# WIFI_Module_Page.net
KiCad netlist of a schematic drawn in Altium Designer
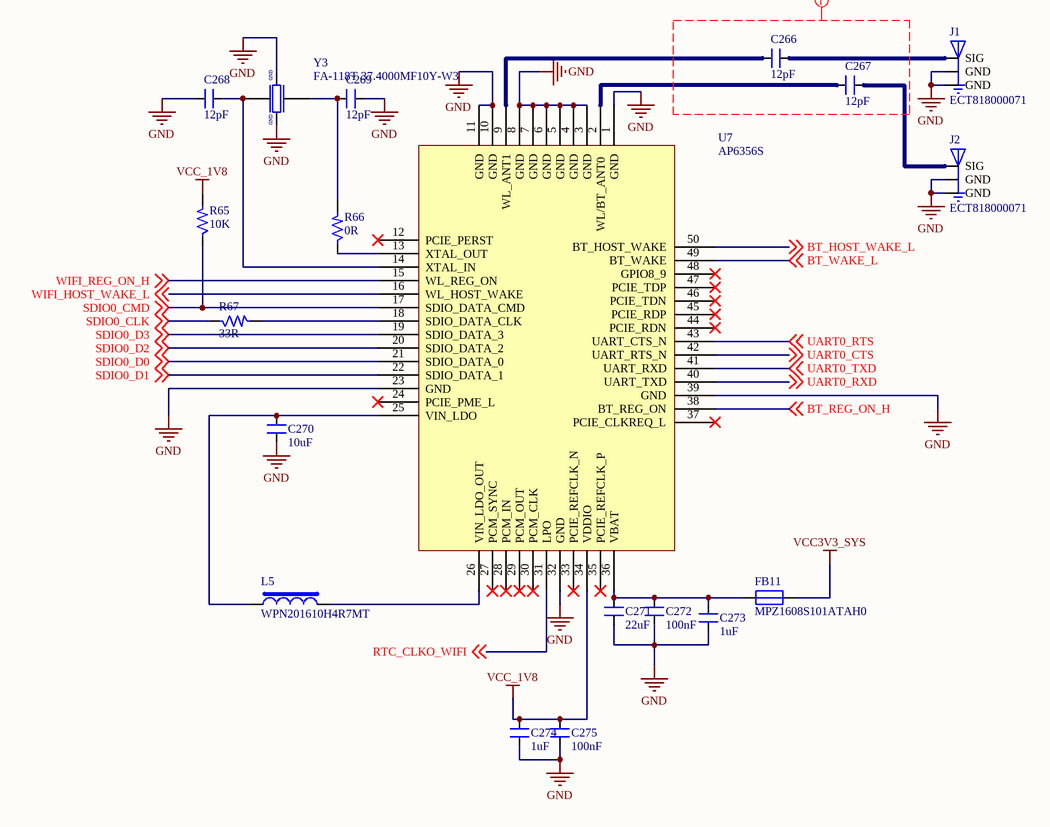
[diagram p0: WIFI Module Page.SchDoc]

(export (version "E")
  (design (tool "Eeschema 10.0.6"))
  (components
    (comp (ref "C266")
      (value "12pF")
      (footprint "CAP_0603")
      (description "12pF ±10% 10V Ceramic Capacitor X8R 0603 (1608 Metric)")
      (fields
        (field (name "MANUFACTURER") "KEMET")
        (field (name "MANUFACTURER PART NUMBER") "C0603X120K8HAC7867")
      )
      (libsource (lib "RK3399 _Module_Schlib") (part "CAP_12pF-10V-10%-0603"))
    )
    (comp (ref "C267")
      (value "12pF")
      (footprint "CAP_0603")
      (description "12pF ±10% 10V Ceramic Capacitor X8R 0603 (1608 Metric)")
      (fields
        (field (name "MANUFACTURER") "KEMET")
        (field (name "MANUFACTURER PART NUMBER") "C0603X120K8HAC7867")
      )
      (libsource (lib "RK3399 _Module_Schlib") (part "CAP_12pF-10V-10%-0603"))
    )
    (comp (ref "C268")
      (value "12pF")
      (footprint "CAP_0603")
      (description "12pF ±10% 10V Ceramic Capacitor X8R 0603 (1608 Metric)")
      (fields
        (field (name "MANUFACTURER") "KEMET")
        (field (name "MANUFACTURER PART NUMBER") "C0603X120K8HAC7867")
      )
      (libsource (lib "RK3399 _Module_Schlib") (part "CAP_12pF-10V-10%-0603"))
    )
    (comp (ref "C269")
      (value "12pF")
      (footprint "CAP_0603")
      (description "12pF ±10% 10V Ceramic Capacitor X8R 0603 (1608 Metric)")
      (fields
        (field (name "MANUFACTURER") "KEMET")
        (field (name "MANUFACTURER PART NUMBER") "C0603X120K8HAC7867")
      )
      (libsource (lib "RK3399 _Module_Schlib") (part "CAP_12pF-10V-10%-0603"))
    )
    (comp (ref "C270")
      (value "10uF")
      (footprint "CAP_0603")
      (description "10µF ±10% 10V Ceramic Capacitor X5R 0603 (1608 Metric)")
      (fields
        (field (name "MANUFACTURER PART NUMBER") "GRM188R61A106KE69J")
        (field (name "MANUFACTURER") "Murata Electronics")
      )
      (libsource (lib "RK3399 _Module_Schlib") (part "CAP_10uF-10V-10%-0603"))
    )
    (comp (ref "C271")
      (value "22uF")
      (footprint "CAP_0603")
      (description "22µF ±20% 10V Ceramic Capacitor X5R 0603 (1608 Metric)")
      (fields
        (field (name "MANUFACTURER") "Murata Electronics")
        (field (name "MANUFACTURER PART NUMBER") "GRM188R61A226ME15D")
      )
      (libsource (lib "RK3399 _Module_Schlib") (part "CAP_22uF-10V-20%-0603"))
    )
    (comp (ref "C272")
      (value "100nF")
      (footprint "CAP_0805")
      (description "0.1µF ±10% 25V Ceramic Capacitor X7R 0805 (2012 Metric)")
      (fields
        (field (name "MANUFACTURER") "Yageo")
        (field (name "MANUFACTURER PART NUMBER") "CC0805KRX7R8BB104")
      )
      (libsource (lib "RK3399 _Module_Schlib") (part "CAP_100nF-25V-10%-0805"))
    )
    (comp (ref "C273")
      (value "1uF")
      (footprint "CAP_0603")
      (description "1µF ±10% 16V Ceramic Capacitor X7R 0603 (1608 Metric)")
      (fields
        (field (name "MANUFACTURER") "Yageo")
        (field (name "MANUFACTURER PART NUMBER") "CC0603KRX7R7BB105")
      )
      (libsource (lib "RK3399 _Module_Schlib") (part "CAP_1uF-16V-10%-0603"))
    )
    (comp (ref "C274")
      (value "1uF")
      (footprint "CAP_0603")
      (description "1µF ±10% 16V Ceramic Capacitor X7R 0603 (1608 Metric)")
      (fields
        (field (name "MANUFACTURER") "Yageo")
        (field (name "MANUFACTURER PART NUMBER") "CC0603KRX7R7BB105")
      )
      (libsource (lib "RK3399 _Module_Schlib") (part "CAP_1uF-16V-10%-0603"))
    )
    (comp (ref "C275")
      (value "100nF")
      (footprint "CAP_0805")
      (description "0.1µF ±10% 25V Ceramic Capacitor X7R 0805 (2012 Metric)")
      (fields
        (field (name "MANUFACTURER") "Yageo")
        (field (name "MANUFACTURER PART NUMBER") "CC0805KRX7R8BB104")
      )
      (libsource (lib "RK3399 _Module_Schlib") (part "CAP_100nF-25V-10%-0805"))
    )
    (comp (ref "FB11")
      (value "MPZ1608S101ATAH0")
      (footprint "RES_0603")
      (description "Ferrite Beads 100ohms 3A 30mOhms 0603 Ferrite Chip")
      (fields (field (name "MANUFACTURER") "TDK"))
      (libsource (lib "RK3399 _Module_Schlib") (part "FB_100R-3A-100Mhz-0603"))
    )
    (comp (ref "J1")
      (value "ECT818000071")
      (footprint "CON3_UFL_116_SMD_ST")
      (description "SMD RF Connectors/Coaxial Connectors RoHS")
      (fields (field (name "MANUFACTURER") "ECT"))
      (libsource (lib "RK3399 _Module_Schlib") (part "CON-PLG_3X1-ECT818000071-ST-SMD"))
    )
    (comp (ref "J2")
      (value "ECT818000071")
      (footprint "CON3_UFL_116_SMD_ST")
      (description "SMD RF Connectors/Coaxial Connectors RoHS")
      (fields (field (name "MANUFACTURER") "ECT"))
      (libsource (lib "RK3399 _Module_Schlib") (part "CON-PLG_3X1-ECT818000071-ST-SMD"))
    )
    (comp (ref "L5")
      (value "WPN201610H4R7MT")
      (footprint "IND_62.9_110X86.6_SMD")
      (description "4.7uH ±20% 900mA 425mΩ SMD,2.0x1.6x1.0mm Power Inductors RoHS")
      (fields (field (name "MANUFACTURER") "Sunlord"))
      (libsource (lib "RK3399 _Module_Schlib") (part "IND_4.7uH-0.9A-20%-SMD"))
    )
    (comp (ref "R65")
      (value "10K")
      (footprint "RES_0603")
      (description "10 kOhms ±1% 0.1W, 1/10W Chip Resistor 0603 (1608 Metric) Thick Film")
      (fields
        (field (name "MANUFACTURER") "Yageo")
        (field (name "MANUFACTURER PART NUMBER") "RC0603FR-0710KL")
      )
      (libsource (lib "RK3399 _Module_Schlib") (part "RES_10K-0.1W-1%-0603"))
    )
    (comp (ref "R66")
      (value "0R")
      (footprint "RES_0603")
      (description "0 Ohms Jumper 0.1W, 1/10W Chip Resistor 0603 (1608 Metric) Thick Film")
      (fields
        (field (name "MANUFACTURER") "Yageo")
        (field (name "MANUFACTURER PART NUMBER") "RC0603JR-070RL")
      )
      (libsource (lib "RK3399 _Module_Schlib") (part "RES_0R-0.1W-1%-0603"))
    )
    (comp (ref "R67")
      (value "33R")
      (footprint "RES_0402")
      (description "33 Ohms ±1% 0.1W, 1/10W Chip Resistor 0402 (1005 Metric) Automotive AEC-Q200 Thick Film")
      (fields
        (field (name "MANUFACTURER") "Panasonic Electronic Components")
        (field (name "MANUFACTURER PART NUMBER") "ERJ-2RKF33R0X")
      )
      (libsource (lib "RK3399 _Module_Schlib") (part "RES_33R-0.1W-1%-0402"))
    )
    (comp (ref "U7")
      (value "AP6356S")
      (footprint "QFN127P600-8N")
      (fields (field (name "MANUFACTURER") "Rockchip"))
      (libsource (lib "RK3399 _Module_Schlib") (part "IC_AP6356S"))
    )
    (comp (ref "Y3")
      (value "FA-118T 37.4000MF10Y-W3")
      (footprint "XTAL_FA-118T 37.4000MF10Y-W3")
      (description "Crystals 37.4MHz 10ppm 12pF -30C +85C")
      (fields (field (name "MANUFACTURER") "Epson Timing"))
      (libsource (lib "RK3399 _Module_Schlib") (part "XTAL_37.4 MHz-12pF-SMD"))
    )
  )
  (nets
    (net (code "1") (name "BT_HOST_WAKE_L") (class "Default")
      (node (ref "U7") (pin "50") (pinfunction "BT_HOST_WAKE_50") (pintype "passive"))
    )
    (net (code "2") (name "BT_REG_ON_H") (class "Default")
      (node (ref "U7") (pin "38") (pinfunction "BT_REG_ON_38") (pintype "passive"))
    )
    (net (code "3") (name "BT_WAKE_L") (class "Default")
      (node (ref "U7") (pin "49") (pinfunction "BT_WAKE_49") (pintype "passive"))
    )
    (net (code "4") (name "GND") (class "Default")
      (node (ref "C268") (pin "1") (pinfunction "1_1") (pintype "passive"))
      (node (ref "C269") (pin "2") (pinfunction "2_2") (pintype "passive"))
      (node (ref "C270") (pin "1") (pinfunction "1_1") (pintype "passive"))
      (node (ref "C271") (pin "1") (pinfunction "1_1") (pintype "passive"))
      (node (ref "C272") (pin "1") (pinfunction "1_1") (pintype "passive"))
      (node (ref "C273") (pin "1") (pinfunction "1_1") (pintype "passive"))
      (node (ref "C274") (pin "1") (pinfunction "1_1") (pintype "passive"))
      (node (ref "C275") (pin "1") (pinfunction "1_1") (pintype "passive"))
      (node (ref "J1") (pin "1") (pinfunction "GND_1") (pintype "passive"))
      (node (ref "J1") (pin "3") (pinfunction "GND_3") (pintype "passive"))
      (node (ref "J2") (pin "1") (pinfunction "GND_1") (pintype "passive"))
      (node (ref "J2") (pin "3") (pinfunction "GND_3") (pintype "passive"))
      (node (ref "U7") (pin "1") (pinfunction "GND_1") (pintype "passive"))
      (node (ref "U7") (pin "10") (pinfunction "GND_10") (pintype "passive"))
      (node (ref "U7") (pin "11") (pinfunction "GND_11") (pintype "passive"))
      (node (ref "U7") (pin "23") (pinfunction "GND_23") (pintype "passive"))
      (node (ref "U7") (pin "3") (pinfunction "GND_3") (pintype "passive"))
      (node (ref "U7") (pin "32") (pinfunction "GND_32") (pintype "passive"))
      (node (ref "U7") (pin "39") (pinfunction "GND_39") (pintype "passive"))
      (node (ref "U7") (pin "4") (pinfunction "GND_4") (pintype "passive"))
      (node (ref "U7") (pin "5") (pinfunction "GND_5") (pintype "passive"))
      (node (ref "U7") (pin "6") (pinfunction "GND_6") (pintype "passive"))
      (node (ref "U7") (pin "7") (pinfunction "GND_7") (pintype "passive"))
      (node (ref "U7") (pin "8") (pinfunction "GND_8") (pintype "passive"))
      (node (ref "Y3") (pin "2") (pinfunction "2_2") (pintype "passive"))
      (node (ref "Y3") (pin "4") (pinfunction "4_4") (pintype "passive"))
    )
    (net (code "5") (name "Net-(C269-Pad1)") (class "Default")
      (node (ref "C269") (pin "1") (pinfunction "1_1") (pintype "passive"))
      (node (ref "R66") (pin "2") (pinfunction "2_2") (pintype "passive"))
      (node (ref "Y3") (pin "3") (pinfunction "3_3") (pintype "passive"))
    )
    (net (code "6") (name "Net-(J1-SIG)") (class "Default")
      (node (ref "C266") (pin "2") (pinfunction "2_2") (pintype "passive"))
      (node (ref "J1") (pin "2") (pinfunction "SIG_2") (pintype "passive"))
    )
    (net (code "7") (name "Net-(J2-SIG)") (class "Default")
      (node (ref "C267") (pin "2") (pinfunction "2_2") (pintype "passive"))
      (node (ref "J2") (pin "2") (pinfunction "SIG_2") (pintype "passive"))
    )
    (net (code "8") (name "Net-(U7-SDIO_DATA_CLK)") (class "Default")
      (node (ref "R67") (pin "2") (pinfunction "2_2") (pintype "passive"))
      (node (ref "U7") (pin "18") (pinfunction "SDIO_DATA_CLK_18") (pintype "passive"))
    )
    (net (code "9") (name "Net-(U7-VBAT)") (class "Default")
      (node (ref "C271") (pin "2") (pinfunction "2_2") (pintype "passive"))
      (node (ref "C272") (pin "2") (pinfunction "2_2") (pintype "passive"))
      (node (ref "C273") (pin "2") (pinfunction "2_2") (pintype "passive"))
      (node (ref "FB11") (pin "1") (pinfunction "1_1") (pintype "passive"))
      (node (ref "U7") (pin "36") (pinfunction "VBAT_36") (pintype "passive"))
    )
    (net (code "10") (name "Net-(U7-VIN_LDO)") (class "Default")
      (node (ref "C270") (pin "2") (pinfunction "2_2") (pintype "passive"))
      (node (ref "L5") (pin "1") (pinfunction "1_1") (pintype "passive"))
      (node (ref "U7") (pin "25") (pinfunction "VIN_LDO_25") (pintype "passive"))
    )
    (net (code "11") (name "Net-(U7-VIN_LDO_OUT)") (class "Default")
      (node (ref "L5") (pin "2") (pinfunction "2_2") (pintype "passive"))
      (node (ref "U7") (pin "26") (pinfunction "VIN_LDO_OUT_26") (pintype "passive"))
    )
    (net (code "12") (name "Net-(U7-WL_ANT1)") (class "Default")
      (node (ref "C266") (pin "1") (pinfunction "1_1") (pintype "passive"))
      (node (ref "U7") (pin "9") (pinfunction "WL_ANT1_9") (pintype "passive"))
    )
    (net (code "13") (name "Net-(U7-WL{slash}BT_ANT0)") (class "Default")
      (node (ref "C267") (pin "1") (pinfunction "1_1") (pintype "passive"))
      (node (ref "U7") (pin "2") (pinfunction "WL/BT_ANT0_2") (pintype "passive"))
    )
    (net (code "14") (name "Net-(U7-XTAL_IN)") (class "Default")
      (node (ref "C268") (pin "2") (pinfunction "2_2") (pintype "passive"))
      (node (ref "U7") (pin "14") (pinfunction "XTAL_IN_14") (pintype "passive"))
      (node (ref "Y3") (pin "1") (pinfunction "1_1") (pintype "passive"))
    )
    (net (code "15") (name "Net-(U7-XTAL_OUT)") (class "Default")
      (node (ref "R66") (pin "1") (pinfunction "1_1") (pintype "passive"))
      (node (ref "U7") (pin "13") (pinfunction "XTAL_OUT_13") (pintype "passive"))
    )
    (net (code "16") (name "RTC_CLKO_WIFI") (class "Default")
      (node (ref "U7") (pin "31") (pinfunction "LPO_31") (pintype "passive"))
    )
    (net (code "17") (name "SDIO0_CLK") (class "Default")
      (node (ref "R67") (pin "1") (pinfunction "1_1") (pintype "passive"))
    )
    (net (code "18") (name "SDIO0_CMD") (class "Default")
      (node (ref "R65") (pin "1") (pinfunction "1_1") (pintype "passive"))
      (node (ref "U7") (pin "17") (pinfunction "SDIO_DATA_CMD_17") (pintype "passive"))
    )
    (net (code "19") (name "SDIO0_D0") (class "Default")
      (node (ref "U7") (pin "21") (pinfunction "SDIO_DATA_0_21") (pintype "passive"))
    )
    (net (code "20") (name "SDIO0_D1") (class "Default")
      (node (ref "U7") (pin "22") (pinfunction "SDIO_DATA_1_22") (pintype "passive"))
    )
    (net (code "21") (name "SDIO0_D2") (class "Default")
      (node (ref "U7") (pin "20") (pinfunction "SDIO_DATA_2_20") (pintype "passive"))
    )
    (net (code "22") (name "SDIO0_D3") (class "Default")
      (node (ref "U7") (pin "19") (pinfunction "SDIO_DATA_3_19") (pintype "passive"))
    )
    (net (code "23") (name "UART0_CTS") (class "Default")
      (node (ref "U7") (pin "42") (pinfunction "UART_RTS_N_42") (pintype "passive"))
    )
    (net (code "24") (name "UART0_RTS") (class "Default")
      (node (ref "U7") (pin "43") (pinfunction "UART_CTS_N_43") (pintype "passive"))
    )
    (net (code "25") (name "UART0_RXD") (class "Default")
      (node (ref "U7") (pin "40") (pinfunction "UART_TXD_40") (pintype "passive"))
    )
    (net (code "26") (name "UART0_TXD") (class "Default")
      (node (ref "U7") (pin "41") (pinfunction "UART_RXD_41") (pintype "passive"))
    )
    (net (code "27") (name "VCC3V3_SYS") (class "Default")
      (node (ref "FB11") (pin "2") (pinfunction "2_2") (pintype "passive"))
    )
    (net (code "28") (name "VCC_1V8") (class "Default")
      (node (ref "C274") (pin "2") (pinfunction "2_2") (pintype "passive"))
      (node (ref "C275") (pin "2") (pinfunction "2_2") (pintype "passive"))
      (node (ref "R65") (pin "2") (pinfunction "2_2") (pintype "passive"))
      (node (ref "U7") (pin "34") (pinfunction "VDDIO_34") (pintype "passive"))
    )
    (net (code "29") (name "WIFI_HOST_WAKE_L") (class "Default")
      (node (ref "U7") (pin "16") (pinfunction "WL_HOST_WAKE_16") (pintype "passive"))
    )
    (net (code "30") (name "WIFI_REG_ON_H") (class "Default")
      (node (ref "U7") (pin "15") (pinfunction "WL_REG_ON_15") (pintype "passive"))
    )
    (net (code "31") (name "unconnected-(U7-GPIO8_9-Pad48)") (class "Default")
      (node (ref "U7") (pin "48") (pinfunction "GPIO8_9_48") (pintype "passive+no_connect"))
    )
    (net (code "32") (name "unconnected-(U7-PCIE_CLKREQ_L-Pad37)") (class "Default")
      (node (ref "U7") (pin "37") (pinfunction "PCIE_CLKREQ_L_37") (pintype "passive+no_connect"))
    )
    (net (code "33") (name "unconnected-(U7-PCIE_PERST-Pad12)") (class "Default")
      (node (ref "U7") (pin "12") (pinfunction "PCIE_PERST_12") (pintype "passive+no_connect"))
    )
    (net (code "34") (name "unconnected-(U7-PCIE_PME_L-Pad24)") (class "Default")
      (node (ref "U7") (pin "24") (pinfunction "PCIE_PME_L_24") (pintype "passive+no_connect"))
    )
    (net (code "35") (name "unconnected-(U7-PCIE_RDN-Pad44)") (class "Default")
      (node (ref "U7") (pin "44") (pinfunction "PCIE_RDN_44") (pintype "passive+no_connect"))
    )
    (net (code "36") (name "unconnected-(U7-PCIE_RDP-Pad45)") (class "Default")
      (node (ref "U7") (pin "45") (pinfunction "PCIE_RDP_45") (pintype "passive+no_connect"))
    )
    (net (code "37") (name "unconnected-(U7-PCIE_REFCLK_N-Pad33)") (class "Default")
      (node (ref "U7") (pin "33") (pinfunction "PCIE_REFCLK_N_33") (pintype "passive+no_connect"))
    )
    (net (code "38") (name "unconnected-(U7-PCIE_REFCLK_P-Pad35)") (class "Default")
      (node (ref "U7") (pin "35") (pinfunction "PCIE_REFCLK_P_35") (pintype "passive+no_connect"))
    )
    (net (code "39") (name "unconnected-(U7-PCIE_TDN-Pad46)") (class "Default")
      (node (ref "U7") (pin "46") (pinfunction "PCIE_TDN_46") (pintype "passive+no_connect"))
    )
    (net (code "40") (name "unconnected-(U7-PCIE_TDP-Pad47)") (class "Default")
      (node (ref "U7") (pin "47") (pinfunction "PCIE_TDP_47") (pintype "passive+no_connect"))
    )
    (net (code "41") (name "unconnected-(U7-PCM_CLK-Pad30)") (class "Default")
      (node (ref "U7") (pin "30") (pinfunction "PCM_CLK_30") (pintype "passive+no_connect"))
    )
    (net (code "42") (name "unconnected-(U7-PCM_IN-Pad28)") (class "Default")
      (node (ref "U7") (pin "28") (pinfunction "PCM_IN_28") (pintype "passive+no_connect"))
    )
    (net (code "43") (name "unconnected-(U7-PCM_OUT-Pad29)") (class "Default")
      (node (ref "U7") (pin "29") (pinfunction "PCM_OUT_29") (pintype "passive+no_connect"))
    )
    (net (code "44") (name "unconnected-(U7-PCM_SYNC-Pad27)") (class "Default")
      (node (ref "U7") (pin "27") (pinfunction "PCM_SYNC_27") (pintype "passive+no_connect"))
    )
  )
)
